# MOD_BOTONES.net
KiCad netlist of a schematic drawn in Altium Designer
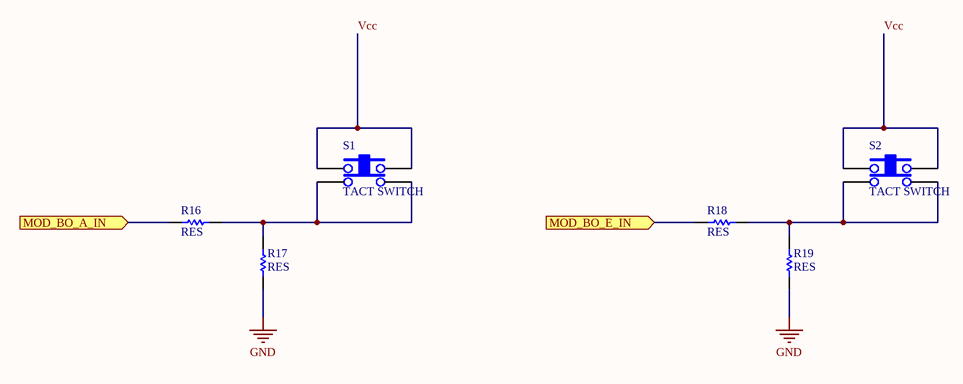
[diagram p0: MOD_BOTONES.SchDoc]

(export (version "E")
  (design (tool "Eeschema 10.0.6"))
  (components
    (comp (ref "R16") (value "RES") (footprint "0805") (libsource (lib "LIBEBAL") (part "RES")))
    (comp (ref "R17") (value "RES") (footprint "0805") (libsource (lib "LIBEBAL") (part "RES")))
    (comp (ref "R18") (value "RES") (footprint "0805") (libsource (lib "LIBEBAL") (part "RES")))
    (comp (ref "R19") (value "RES") (footprint "0805") (libsource (lib "LIBEBAL") (part "RES")))
    (comp (ref "S1")
      (value "TACT SWITCH")
      (footprint "TACTSWITCH")
      (libsource (lib "LIB PIO IX") (part "TACT SWITCH"))
    )
    (comp (ref "S2")
      (value "TACT SWITCH")
      (footprint "TACTSWITCH")
      (libsource (lib "LIB PIO IX") (part "TACT SWITCH"))
    )
  )
  (nets
    (net (code "1") (name "/MOD_BO_A_IN") (class "Default")
      (node (ref "R16") (pin "1") (pinfunction "1_1") (pintype "passive"))
    )
    (net (code "2") (name "/MOD_BO_E_IN") (class "Default")
      (node (ref "R18") (pin "1") (pinfunction "1_1") (pintype "passive"))
    )
    (net (code "3") (name "/Vcc") (class "Default")
      (node (ref "S1") (pin "1") (pinfunction "1_1") (pintype "passive"))
      (node (ref "S1") (pin "3") (pinfunction "3_3") (pintype "passive"))
      (node (ref "S2") (pin "1") (pinfunction "1_1") (pintype "passive"))
      (node (ref "S2") (pin "3") (pinfunction "3_3") (pintype "passive"))
    )
    (net (code "4") (name "GND") (class "Default")
      (node (ref "R17") (pin "1") (pinfunction "1_1") (pintype "passive"))
      (node (ref "R19") (pin "1") (pinfunction "1_1") (pintype "passive"))
    )
    (net (code "5") (name "Net-(R16-Pad2)") (class "Default")
      (node (ref "R16") (pin "2") (pinfunction "2_2") (pintype "passive"))
      (node (ref "R17") (pin "2") (pinfunction "2_2") (pintype "passive"))
      (node (ref "S1") (pin "2") (pinfunction "2_2") (pintype "passive"))
      (node (ref "S1") (pin "4") (pinfunction "4_4") (pintype "passive"))
    )
    (net (code "6") (name "Net-(R18-Pad2)") (class "Default")
      (node (ref "R18") (pin "2") (pinfunction "2_2") (pintype "passive"))
      (node (ref "R19") (pin "2") (pinfunction "2_2") (pintype "passive"))
      (node (ref "S2") (pin "2") (pinfunction "2_2") (pintype "passive"))
      (node (ref "S2") (pin "4") (pinfunction "4_4") (pintype "passive"))
    )
  )
)
